# Acoustics_Board_Sheet_1.net
KiCad netlist of a schematic drawn in Altium Designer
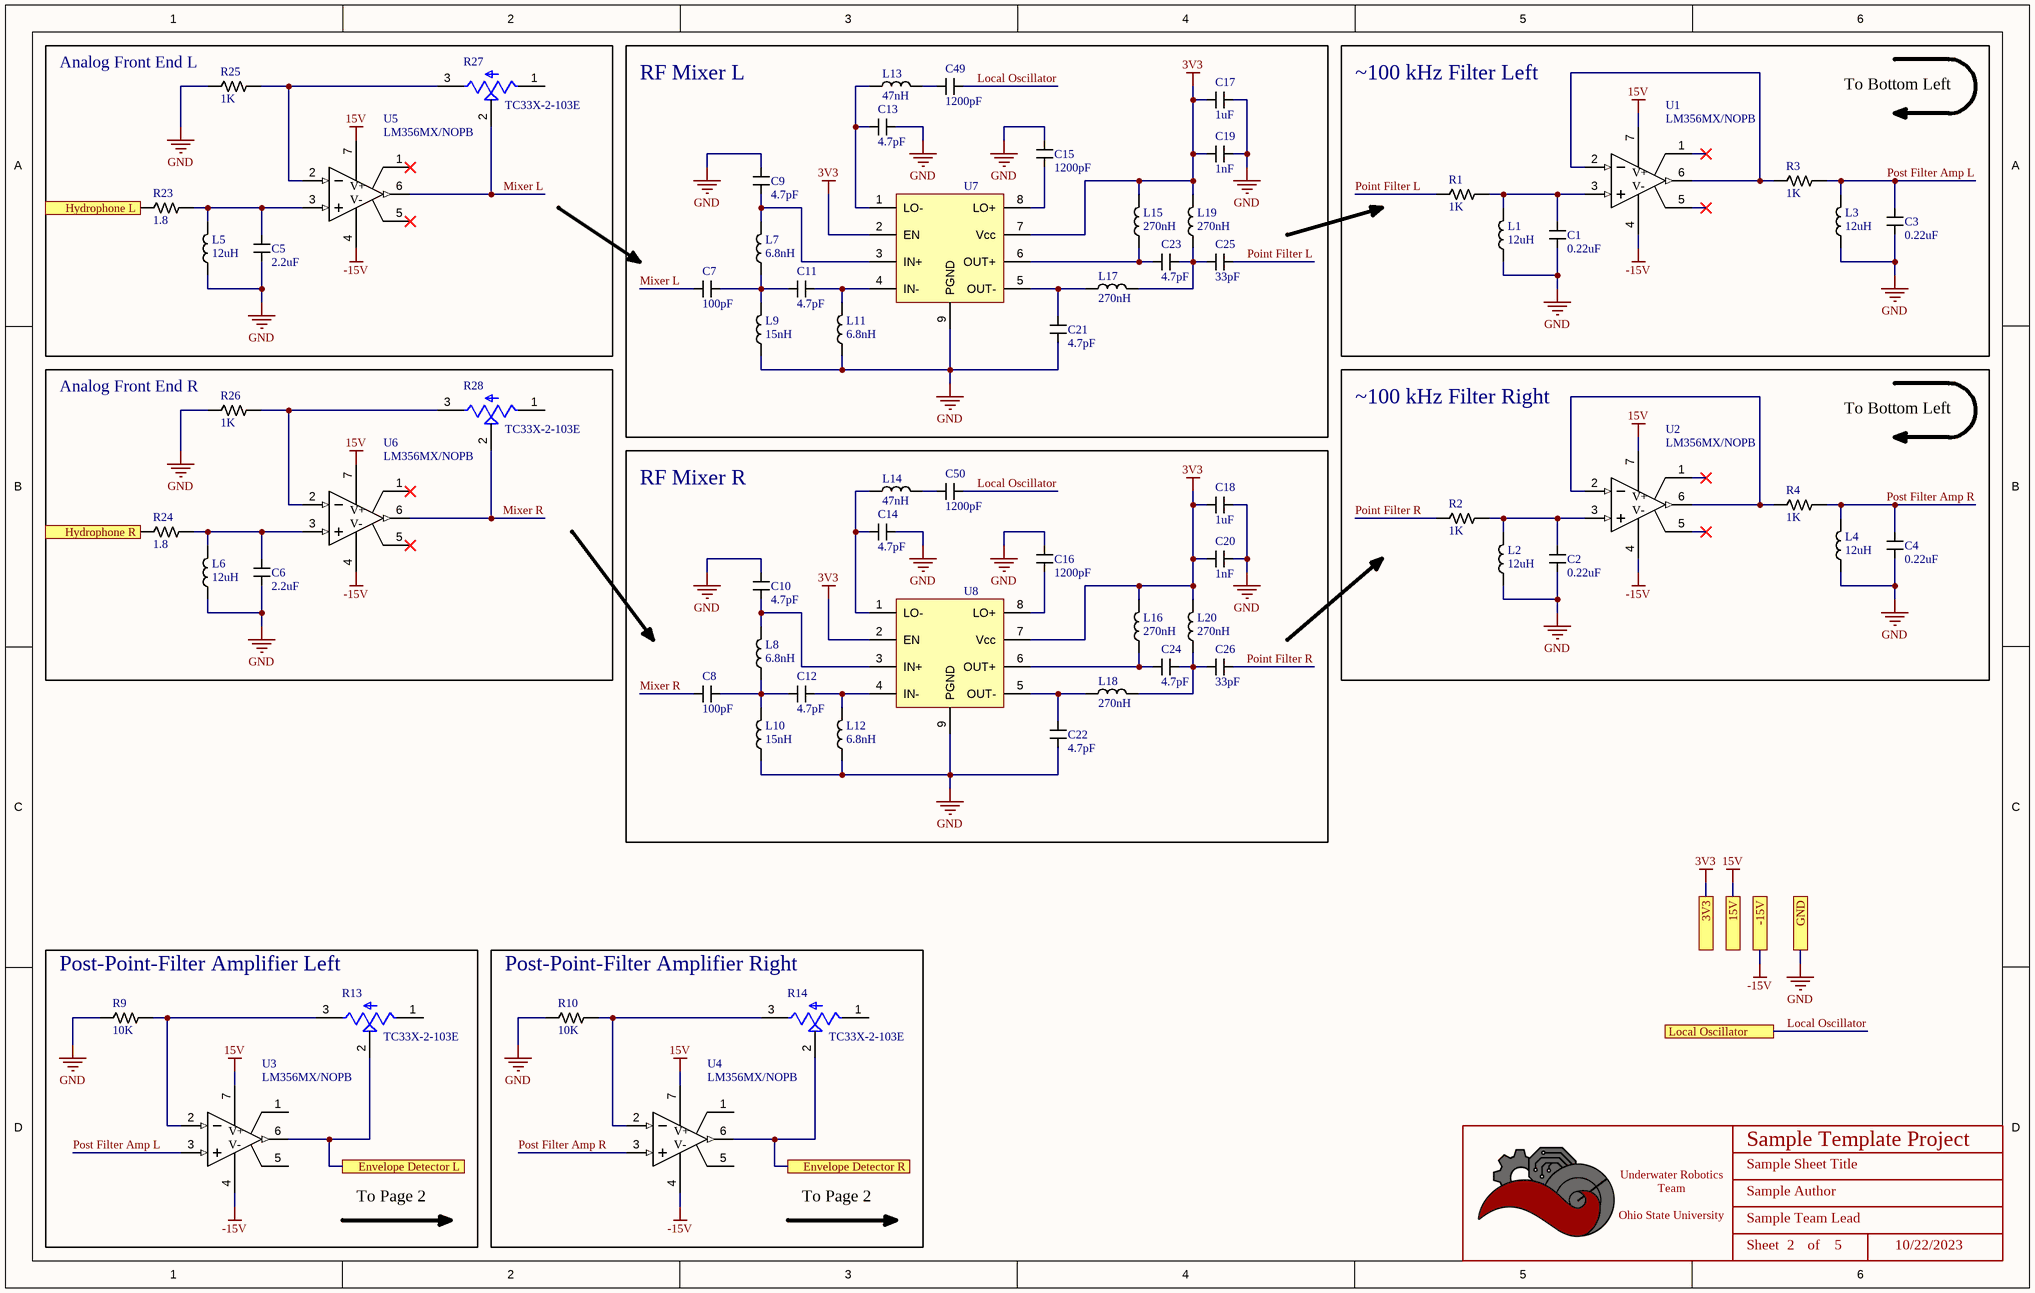
[diagram p0: Acoustics Board Sheet 1.SchDoc]

(export (version "E")
  (design (tool "Eeschema 10.0.6"))
  (components
    (comp (ref "C1")
      (value "0.22uF")
      (footprint "CAPACITOR_0603")
      (description "CAP CER 0.22uF 16V X7R 0603")
      (fields
        (field (name "TOLERANCE") "+/- 5%")
        (field (name "VOLTAGE") "16V")
        (field (name "MADE BY") "Nathan Ayer")
      )
      (libsource (lib "Capacitors") (part "CAPACITOR_0.000027uF_0603"))
    )
    (comp (ref "C2")
      (value "0.22uF")
      (footprint "CAPACITOR_0603")
      (description "CAP CER 0.22uF 16V X7R 0603")
      (fields
        (field (name "TOLERANCE") "+/- 5%")
        (field (name "VOLTAGE") "16V")
        (field (name "MADE BY") "Nathan Ayer")
      )
      (libsource (lib "Capacitors") (part "CAPACITOR_0.000027uF_0603"))
    )
    (comp (ref "C3")
      (value "0.22uF")
      (footprint "CAPACITOR_0603")
      (description "CAP CER 0.22uF 16V X7R 0603")
      (fields
        (field (name "TOLERANCE") "+/- 5%")
        (field (name "VOLTAGE") "16V")
        (field (name "MADE BY") "Nathan Ayer")
      )
      (libsource (lib "Capacitors") (part "CAPACITOR_0.000027uF_0603"))
    )
    (comp (ref "C4")
      (value "0.22uF")
      (footprint "CAPACITOR_0603")
      (description "CAP CER 0.22uF 16V X7R 0603")
      (fields
        (field (name "TOLERANCE") "+/- 5%")
        (field (name "VOLTAGE") "16V")
        (field (name "MADE BY") "Nathan Ayer")
      )
      (libsource (lib "Capacitors") (part "CAPACITOR_0.000027uF_0603"))
    )
    (comp (ref "C5")
      (value "2.2uF")
      (footprint "CAPACITOR_0603")
      (description "CAP CER 2.2PF 50V C0G/NP0 0603")
      (fields
        (field (name "TOLERANCE") "+/- 20%")
        (field (name "VOLTAGE") "6.3V")
        (field (name "MADE BY") "Flip B")
      )
      (libsource (lib "Capacitors") (part "CAPACITOR_22uF_0603"))
    )
    (comp (ref "C6")
      (value "2.2uF")
      (footprint "CAPACITOR_0603")
      (description "CAP CER 2.2PF 50V C0G/NP0 0603")
      (fields
        (field (name "TOLERANCE") "+/- 20%")
        (field (name "VOLTAGE") "6.3V")
        (field (name "MADE BY") "Flip B")
      )
      (libsource (lib "Capacitors") (part "CAPACITOR_22uF_0603"))
    )
    (comp (ref "C7")
      (value "100pF")
      (footprint "CAPACITOR_0402")
      (description "Cap 100pF 25V +/-10%\r\nCeramic 0402")
      (fields
        (field (name "TOLERANCE") "+/- 10%")
        (field (name "VOLTAGE") "25V")
        (field (name "MADE BY") "Robert Pafford")
      )
      (libsource (lib "Capacitors") (part "CAPACITOR_0.0001uF_0402"))
    )
    (comp (ref "C8")
      (value "100pF")
      (footprint "CAPACITOR_0402")
      (description "Cap 100pF 25V +/-10%\r\nCeramic 0402")
      (fields
        (field (name "TOLERANCE") "+/- 10%")
        (field (name "VOLTAGE") "25V")
        (field (name "MADE BY") "Robert Pafford")
      )
      (libsource (lib "Capacitors") (part "CAPACITOR_0.0001uF_0402"))
    )
    (comp (ref "C9")
      (value "4.7pF")
      (footprint "CAPACITOR_0402")
      (description "4.7 pF ±0.1pF 50V Ceramic Capacitor C0G, NP0 0402 (1005 Metric)")
      (fields (field (name "TOLERANCE") "+/- 0.1 pF") (field (name "VOLTAGE") "50V"))
      (libsource (lib "Capacitors") (part "CAPACITOR_0.000015uF_0402"))
    )
    (comp (ref "C10")
      (value "4.7pF")
      (footprint "CAPACITOR_0402")
      (description "4.7 pF ±0.1pF 50V Ceramic Capacitor C0G, NP0 0402 (1005 Metric)")
      (fields (field (name "TOLERANCE") "+/- 0.1 pF") (field (name "VOLTAGE") "50V"))
      (libsource (lib "Capacitors") (part "CAPACITOR_0.000015uF_0402"))
    )
    (comp (ref "C11")
      (value "4.7pF")
      (footprint "CAPACITOR_0402")
      (description "4.7 pF ±0.1pF 50V Ceramic Capacitor C0G, NP0 0402 (1005 Metric)")
      (fields (field (name "TOLERANCE") "+/- 0.1 pF") (field (name "VOLTAGE") "50V"))
      (libsource (lib "Capacitors") (part "CAPACITOR_0.000015uF_0402"))
    )
    (comp (ref "C12")
      (value "4.7pF")
      (footprint "CAPACITOR_0402")
      (description "4.7 pF ±0.1pF 50V Ceramic Capacitor C0G, NP0 0402 (1005 Metric)")
      (fields (field (name "TOLERANCE") "+/- 0.1 pF") (field (name "VOLTAGE") "50V"))
      (libsource (lib "Capacitors") (part "CAPACITOR_0.000015uF_0402"))
    )
    (comp (ref "C13")
      (value "4.7pF")
      (footprint "CAPACITOR_0402")
      (description "4.7 pF ±0.1pF 50V Ceramic Capacitor C0G, NP0 0402 (1005 Metric)")
      (fields (field (name "TOLERANCE") "+/- 0.1 pF") (field (name "VOLTAGE") "50V"))
      (libsource (lib "Capacitors") (part "CAPACITOR_0.000015uF_0402"))
    )
    (comp (ref "C14")
      (value "4.7pF")
      (footprint "CAPACITOR_0402")
      (description "4.7 pF ±0.1pF 50V Ceramic Capacitor C0G, NP0 0402 (1005 Metric)")
      (fields (field (name "TOLERANCE") "+/- 0.1 pF") (field (name "VOLTAGE") "50V"))
      (libsource (lib "Capacitors") (part "CAPACITOR_0.000015uF_0402"))
    )
    (comp (ref "C15")
      (value "1200pF")
      (footprint "CAPACITOR_0402")
      (description "CAP CER 1200PF 50V X7R 0402")
      (fields
        (field (name "TOLERANCE") "+/- 5%")
        (field (name "VOLTAGE") "50V")
        (field (name "MADE BY") "Robert Pafford")
      )
      (libsource (lib "Capacitors") (part "CAPACITOR_0.0012uF_0402"))
    )
    (comp (ref "C16")
      (value "1200pF")
      (footprint "CAPACITOR_0402")
      (description "CAP CER 1200PF 50V X7R 0402")
      (fields
        (field (name "TOLERANCE") "+/- 5%")
        (field (name "VOLTAGE") "50V")
        (field (name "MADE BY") "Robert Pafford")
      )
      (libsource (lib "Capacitors") (part "CAPACITOR_0.0012uF_0402"))
    )
    (comp (ref "C17")
      (value "1uF")
      (footprint "CAPACITOR_0603")
      (description "Cap 1uF 25V +/-10%\r\nCeramic 0603")
      (fields
        (field (name "TOLERANCE") "+/- 10%")
        (field (name "VOLTAGE") "16V")
        (field (name "MADE BY") "Flip B")
      )
      (libsource (lib "Capacitors") (part "CAPACITOR_1uF_0603_25V"))
    )
    (comp (ref "C18")
      (value "1uF")
      (footprint "CAPACITOR_0603")
      (description "Cap 1uF 25V +/-10%\r\nCeramic 0603")
      (fields
        (field (name "TOLERANCE") "+/- 10%")
        (field (name "VOLTAGE") "16V")
        (field (name "MADE BY") "Flip B")
      )
      (libsource (lib "Capacitors") (part "CAPACITOR_1uF_0603_25V"))
    )
    (comp (ref "C19")
      (value "1nF")
      (footprint "CAPACITOR_0603")
      (description "Cap 1000pF 50V +/-2%\r\nCeramic 0603")
      (fields
        (field (name "TOLERANCE") "+/- 2%")
        (field (name "VOLTAGE") "50")
        (field (name "MADE BY") "Flip B")
      )
      (libsource (lib "Capacitors") (part "CAPACITOR_0.001uF_0603"))
    )
    (comp (ref "C20")
      (value "1nF")
      (footprint "CAPACITOR_0603")
      (description "Cap 1000pF 50V +/-2%\r\nCeramic 0603")
      (fields
        (field (name "TOLERANCE") "+/- 2%")
        (field (name "VOLTAGE") "50")
        (field (name "MADE BY") "Flip B")
      )
      (libsource (lib "Capacitors") (part "CAPACITOR_0.001uF_0603"))
    )
    (comp (ref "C21")
      (value "4.7pF")
      (footprint "CAPACITOR_0402")
      (description "4.7 pF ±0.1pF 50V Ceramic Capacitor C0G, NP0 0402 (1005 Metric)")
      (fields (field (name "TOLERANCE") "+/- 0.1 pF") (field (name "VOLTAGE") "50V"))
      (libsource (lib "Capacitors") (part "CAPACITOR_0.000015uF_0402"))
    )
    (comp (ref "C22")
      (value "4.7pF")
      (footprint "CAPACITOR_0402")
      (description "4.7 pF ±0.1pF 50V Ceramic Capacitor C0G, NP0 0402 (1005 Metric)")
      (fields (field (name "TOLERANCE") "+/- 0.1 pF") (field (name "VOLTAGE") "50V"))
      (libsource (lib "Capacitors") (part "CAPACITOR_0.000015uF_0402"))
    )
    (comp (ref "C23")
      (value "4.7pF")
      (footprint "CAPACITOR_0402")
      (description "4.7 pF ±0.1pF 50V Ceramic Capacitor C0G, NP0 0402 (1005 Metric)")
      (fields (field (name "TOLERANCE") "+/- 0.1 pF") (field (name "VOLTAGE") "50V"))
      (libsource (lib "Capacitors") (part "CAPACITOR_0.000015uF_0402"))
    )
    (comp (ref "C24")
      (value "4.7pF")
      (footprint "CAPACITOR_0402")
      (description "4.7 pF ±0.1pF 50V Ceramic Capacitor C0G, NP0 0402 (1005 Metric)")
      (fields (field (name "TOLERANCE") "+/- 0.1 pF") (field (name "VOLTAGE") "50V"))
      (libsource (lib "Capacitors") (part "CAPACITOR_0.000015uF_0402"))
    )
    (comp (ref "C25")
      (value "33pF")
      (footprint "CAPACITOR_0603")
      (description "33 pF ±5% 250V Ceramic Capacitor C0G, NP0 0603 (1608 Metric)")
      (fields (field (name "TOLERANCE") "+/- 5%") (field (name "VOLTAGE") "250V"))
      (libsource (lib "Capacitors") (part "CAPACITOR_0.001uF_0603"))
    )
    (comp (ref "C26")
      (value "33pF")
      (footprint "CAPACITOR_0603")
      (description "33 pF ±5% 250V Ceramic Capacitor C0G, NP0 0603 (1608 Metric)")
      (fields (field (name "TOLERANCE") "+/- 5%") (field (name "VOLTAGE") "250V"))
      (libsource (lib "Capacitors") (part "CAPACITOR_0.001uF_0603"))
    )
    (comp (ref "C49")
      (value "1200pF")
      (footprint "CAPACITOR_0402")
      (description "CAP CER 1200PF 50V X7R 0402")
      (fields
        (field (name "TOLERANCE") "+/- 5%")
        (field (name "VOLTAGE") "50V")
        (field (name "MADE BY") "Robert Pafford")
      )
      (libsource (lib "Capacitors") (part "CAPACITOR_0.0012uF_0402"))
    )
    (comp (ref "C50")
      (value "1200pF")
      (footprint "CAPACITOR_0402")
      (description "CAP CER 1200PF 50V X7R 0402")
      (fields
        (field (name "TOLERANCE") "+/- 5%")
        (field (name "VOLTAGE") "50V")
        (field (name "MADE BY") "Robert Pafford")
      )
      (libsource (lib "Capacitors") (part "CAPACITOR_0.0012uF_0402"))
    )
    (comp (ref "L1")
      (value "12uH")
      (footprint "INDUCTOR_0603")
      (description "12 µH Shielded Multilayer Inductor 10 mA 1.8Ohm Max 0603 (1608 Metric)")
      (fields
        (field (name "TOLERANCE") "+/- 5%")
        (field (name "Comment") "FIXED IND 12UH 10MA 1.8 OHM SMD")
        (field (name "MADE BY") "Nathan Ayer")
      )
      (libsource (lib "Inductors") (part "INDUCTOR_12uH_0603"))
    )
    (comp (ref "L2")
      (value "12uH")
      (footprint "INDUCTOR_0603")
      (description "12 µH Shielded Multilayer Inductor 10 mA 1.8Ohm Max 0603 (1608 Metric)")
      (fields
        (field (name "TOLERANCE") "+/- 5%")
        (field (name "Comment") "FIXED IND 12UH 10MA 1.8 OHM SMD")
        (field (name "MADE BY") "Nathan Ayer")
      )
      (libsource (lib "Inductors") (part "INDUCTOR_12uH_0603"))
    )
    (comp (ref "L3")
      (value "12uH")
      (footprint "INDUCTOR_0603")
      (description "12 µH Shielded Multilayer Inductor 10 mA 1.8Ohm Max 0603 (1608 Metric)")
      (fields
        (field (name "TOLERANCE") "+/- 5%")
        (field (name "Comment") "FIXED IND 12UH 10MA 1.8 OHM SMD")
        (field (name "MADE BY") "Nathan Ayer")
      )
      (libsource (lib "Inductors") (part "INDUCTOR_12uH_0603"))
    )
    (comp (ref "L4")
      (value "12uH")
      (footprint "INDUCTOR_0603")
      (description "12 µH Shielded Multilayer Inductor 10 mA 1.8Ohm Max 0603 (1608 Metric)")
      (fields
        (field (name "TOLERANCE") "+/- 5%")
        (field (name "Comment") "FIXED IND 12UH 10MA 1.8 OHM SMD")
        (field (name "MADE BY") "Nathan Ayer")
      )
      (libsource (lib "Inductors") (part "INDUCTOR_12uH_0603"))
    )
    (comp (ref "L5")
      (value "12uH")
      (footprint "INDUCTOR_0603")
      (description "12 µH Shielded Multilayer Inductor 10 mA 1.8Ohm Max 0603 (1608 Metric)")
      (fields
        (field (name "TOLERANCE") "+/- 20%")
        (field (name "Comment") "FIXED IND 12UH 10MA 1.8 OHM SMD")
        (field (name "MADE BY") "Robert Pafford")
      )
      (libsource (lib "Inductors") (part "INDUCTOR_12uH_0603"))
    )
    (comp (ref "L6")
      (value "12uH")
      (footprint "INDUCTOR_0603")
      (description "12 µH Shielded Multilayer Inductor 10 mA 1.8Ohm Max 0603 (1608 Metric)")
      (fields
        (field (name "TOLERANCE") "+/- 20%")
        (field (name "Comment") "FIXED IND 12UH 10MA 1.8 OHM SMD")
        (field (name "MADE BY") "Robert Pafford")
      )
      (libsource (lib "Inductors") (part "INDUCTOR_12uH_0603"))
    )
    (comp (ref "L7")
      (value "6.8nH")
      (footprint "INDUCTOR_0402")
      (description "6.8 nH Unshielded Multilayer Inductor 250 mA 320mOhm Max 0402 (1005 Metric)")
      (fields (field (name "TOLERANCE") "+/- 5%") (field (name "Comment") "FIXED IND 6.8NH 250MA 320MOHM SM"))
      (libsource (lib "Inductors") (part "INDUCTOR_15nH_0402"))
    )
    (comp (ref "L8")
      (value "6.8nH")
      (footprint "INDUCTOR_0402")
      (description "6.8 nH Unshielded Multilayer Inductor 250 mA 320mOhm Max 0402 (1005 Metric)")
      (fields (field (name "TOLERANCE") "+/- 5%") (field (name "Comment") "FIXED IND 6.8NH 250MA 320MOHM SM"))
      (libsource (lib "Inductors") (part "INDUCTOR_15nH_0402"))
    )
    (comp (ref "L9")
      (value "15nH")
      (footprint "INDUCTOR_0402")
      (description "15 nH Unshielded Multilayer Inductor 250 mA 600mOhm Max 0402 (1005 Metric)")
      (fields (field (name "TOLERANCE") "+/- 5%") (field (name "Comment") "FIXED IND 15NH 250MA 600MOHM SMD"))
      (libsource (lib "Inductors") (part "INDUCTOR_15nH_0402"))
    )
    (comp (ref "L10")
      (value "15nH")
      (footprint "INDUCTOR_0402")
      (description "15 nH Unshielded Multilayer Inductor 250 mA 600mOhm Max 0402 (1005 Metric)")
      (fields (field (name "TOLERANCE") "+/- 5%") (field (name "Comment") "FIXED IND 15NH 250MA 600MOHM SMD"))
      (libsource (lib "Inductors") (part "INDUCTOR_15nH_0402"))
    )
    (comp (ref "L11")
      (value "6.8nH")
      (footprint "INDUCTOR_0402")
      (description "6.8 nH Unshielded Multilayer Inductor 250 mA 320mOhm Max 0402 (1005 Metric)")
      (fields (field (name "TOLERANCE") "+/- 5%") (field (name "Comment") "FIXED IND 6.8NH 250MA 320MOHM SM"))
      (libsource (lib "Inductors") (part "INDUCTOR_15nH_0402"))
    )
    (comp (ref "L12")
      (value "6.8nH")
      (footprint "INDUCTOR_0402")
      (description "6.8 nH Unshielded Multilayer Inductor 250 mA 320mOhm Max 0402 (1005 Metric)")
      (fields (field (name "TOLERANCE") "+/- 5%") (field (name "Comment") "FIXED IND 6.8NH 250MA 320MOHM SM"))
      (libsource (lib "Inductors") (part "INDUCTOR_15nH_0402"))
    )
    (comp (ref "L13")
      (value "47nH")
      (footprint "INDUCTOR_0402")
      (description "47 nH Unshielded Multilayer Inductor 200 mA 1.1Ohm Max 0402 (1005 Metric)")
      (fields (field (name "TOLERANCE") "+/- 5%") (field (name "Comment") "FIXED IND 47NH 200MA 1.1 OHM SMD"))
      (libsource (lib "Inductors") (part "INDUCTOR_15nH_0402"))
    )
    (comp (ref "L14")
      (value "47nH")
      (footprint "INDUCTOR_0402")
      (description "47 nH Unshielded Multilayer Inductor 200 mA 1.1Ohm Max 0402 (1005 Metric)")
      (fields (field (name "TOLERANCE") "+/- 5%") (field (name "Comment") "FIXED IND 47NH 200MA 1.1 OHM SMD"))
      (libsource (lib "Inductors") (part "INDUCTOR_15nH_0402"))
    )
    (comp (ref "L15")
      (value "270nH")
      (footprint "INDUCTOR_0402")
      (description "270 nH Unshielded Multilayer Inductor 110 mA 4.94Ohm Max 0402 (1005 Metric)")
      (fields
        (field (name "TOLERANCE") "+/- 10%")
        (field (name "Comment") "FIXED IND 270NH 110MA 4.94OHM SM")
      )
      (libsource (lib "Inductors") (part "INDUCTOR_15nH_0402"))
    )
    (comp (ref "L16")
      (value "270nH")
      (footprint "INDUCTOR_0402")
      (description "270 nH Unshielded Multilayer Inductor 110 mA 4.94Ohm Max 0402 (1005 Metric)")
      (fields
        (field (name "TOLERANCE") "+/- 10%")
        (field (name "Comment") "FIXED IND 270NH 110MA 4.94OHM SM")
      )
      (libsource (lib "Inductors") (part "INDUCTOR_15nH_0402"))
    )
    (comp (ref "L17")
      (value "270nH")
      (footprint "INDUCTOR_0402")
      (description "270 nH Unshielded Multilayer Inductor 110 mA 4.94Ohm Max 0402 (1005 Metric)")
      (fields
        (field (name "TOLERANCE") "+/- 10%")
        (field (name "Comment") "FIXED IND 270NH 110MA 4.94OHM SM")
      )
      (libsource (lib "Inductors") (part "INDUCTOR_15nH_0402"))
    )
    (comp (ref "L18")
      (value "270nH")
      (footprint "INDUCTOR_0402")
      (description "270 nH Unshielded Multilayer Inductor 110 mA 4.94Ohm Max 0402 (1005 Metric)")
      (fields
        (field (name "TOLERANCE") "+/- 10%")
        (field (name "Comment") "FIXED IND 270NH 110MA 4.94OHM SM")
      )
      (libsource (lib "Inductors") (part "INDUCTOR_15nH_0402"))
    )
    (comp (ref "L19")
      (value "270nH")
      (footprint "INDUCTOR_0402")
      (description "270 nH Unshielded Multilayer Inductor 110 mA 4.94Ohm Max 0402 (1005 Metric)")
      (fields
        (field (name "TOLERANCE") "+/- 10%")
        (field (name "Comment") "FIXED IND 270NH 110MA 4.94OHM SM")
      )
      (libsource (lib "Inductors") (part "INDUCTOR_15nH_0402"))
    )
    (comp (ref "L20")
      (value "270nH")
      (footprint "INDUCTOR_0402")
      (description "270 nH Unshielded Multilayer Inductor 110 mA 4.94Ohm Max 0402 (1005 Metric)")
      (fields
        (field (name "TOLERANCE") "+/- 10%")
        (field (name "Comment") "FIXED IND 270NH 110MA 4.94OHM SM")
      )
      (libsource (lib "Inductors") (part "INDUCTOR_15nH_0402"))
    )
    (comp (ref "R1")
      (value "1.45k Ohm 0.1% 1/10W")
      (footprint "RESISTOR_0603")
      (description "RES 1.45K OHM 0.1% 1/10W 0603")
      (fields
        (field (name "TOLERANCE") "+/- 0.1%")
        (field (name "VALUE  (OHMS)") "1K")
        (field (name "MADE BY") "Nathan Ayer")
      )
      (libsource (lib "Resistors") (part "RESISTOR_1K_0603"))
    )
    (comp (ref "R2")
      (value "1.45k Ohm 0.1% 1/10W")
      (footprint "RESISTOR_0603")
      (description "RES 1.45K OHM 0.1% 1/10W 0603")
      (fields
        (field (name "TOLERANCE") "+/- 0.1%")
        (field (name "VALUE  (OHMS)") "1K")
        (field (name "MADE BY") "Nathan Ayer")
      )
      (libsource (lib "Resistors") (part "RESISTOR_1K_0603"))
    )
    (comp (ref "R3")
      (value "1.45k Ohm 0.1% 1/10W")
      (footprint "RESISTOR_0603")
      (description "RES 1.45K OHM 0.1% 1/10W 0603")
      (fields
        (field (name "TOLERANCE") "+/- 0.1%")
        (field (name "VALUE  (OHMS)") "1K")
        (field (name "MADE BY") "Nathan Ayer")
      )
      (libsource (lib "Resistors") (part "RESISTOR_1K_0603"))
    )
    (comp (ref "R4")
      (value "1.45k Ohm 0.1% 1/10W")
      (footprint "RESISTOR_0603")
      (description "RES 1.45K OHM 0.1% 1/10W 0603")
      (fields
        (field (name "TOLERANCE") "+/- 0.1%")
        (field (name "VALUE  (OHMS)") "1K")
        (field (name "MADE BY") "Nathan Ayer")
      )
      (libsource (lib "Resistors") (part "RESISTOR_1K_0603"))
    )
    (comp (ref "R9")
      (value "10k Ohm 0.5% 1/10W")
      (footprint "RESISTOR_0603")
      (description "RES 10k OHM 0.5% 1/10W 0603")
      (fields
        (field (name "TOLERANCE") "+/- 0.5%")
        (field (name "VALUE  (OHMS)") "10K")
        (field (name "MADE BY") "Robert Pafford")
      )
      (libsource (lib "Resistors") (part "RESISTOR_10K_0.5%_0603"))
    )
    (comp (ref "R10")
      (value "10k Ohm 0.5% 1/10W")
      (footprint "RESISTOR_0603")
      (description "RES 10k OHM 0.5% 1/10W 0603")
      (fields
        (field (name "TOLERANCE") "+/- 0.5%")
        (field (name "VALUE  (OHMS)") "10K")
        (field (name "MADE BY") "Robert Pafford")
      )
      (libsource (lib "Resistors") (part "RESISTOR_10K_0.5%_0603"))
    )
    (comp (ref "R13")
      (value "TC33X-2-103E")
      (footprint "TRIM_TC33X-2-203E")
      (description "20 kOhms 0.1W, 1/10W J Lead Surface Mount Trimmer Potentiometer Cermet 1 Turn Top Adjustment")
      (fields (field (name "MF") "Bourns") (field (name "DIGI-KEY_PART_NUMBER") "TC33X-2-203ECT-ND"))
      (libsource (lib "Resistors") (part "TC33X-2-203E"))
    )
    (comp (ref "R14")
      (value "TC33X-2-103E")
      (footprint "TRIM_TC33X-2-203E")
      (description "20 kOhms 0.1W, 1/10W J Lead Surface Mount Trimmer Potentiometer Cermet 1 Turn Top Adjustment")
      (fields (field (name "MF") "Bourns") (field (name "DIGI-KEY_PART_NUMBER") "TC33X-2-203ECT-ND"))
      (libsource (lib "Resistors") (part "TC33X-2-203E"))
    )
    (comp (ref "R23")
      (value "2k Ohm 1% 1/16W")
      (footprint "RESISTOR_0402")
      (description "RES 2k OHM 1% 1/16W 0402")
      (fields
        (field (name "TOLERANCE") "+/- 1%")
        (field (name "VALUE  (OHMS)") "1.8")
        (field (name "MADE BY") "Flip B")
      )
      (libsource (lib "Resistors") (part "RESISTOR_2K_0402"))
    )
    (comp (ref "R24")
      (value "2k Ohm 1% 1/16W")
      (footprint "RESISTOR_0402")
      (description "RES 2k OHM 1% 1/16W 0402")
      (fields
        (field (name "TOLERANCE") "+/- 1%")
        (field (name "VALUE  (OHMS)") "1.8")
        (field (name "MADE BY") "Flip B")
      )
      (libsource (lib "Resistors") (part "RESISTOR_2K_0402"))
    )
    (comp (ref "R25")
      (value "1k Ohm 5% 1/8W")
      (footprint "RESISTOR_0603")
      (description "RES 1.8 OHM 5% 1/8W 0603")
      (fields
        (field (name "TOLERANCE") "+/- 5%")
        (field (name "VALUE  (OHMS)") "1K")
        (field (name "MADE BY") "Robert Pafford")
      )
      (libsource (lib "Resistors") (part "RESISTOR_1K_0603"))
    )
    (comp (ref "R26")
      (value "1k Ohm 5% 1/8W")
      (footprint "RESISTOR_0603")
      (description "RES 1k OHM 5% 1/8W 0603")
      (fields
        (field (name "TOLERANCE") "+/- 5%")
        (field (name "VALUE  (OHMS)") "1K")
        (field (name "MADE BY") "Robert Pafford")
      )
      (libsource (lib "Resistors") (part "RESISTOR_1K_0603"))
    )
    (comp (ref "R27")
      (value "TC33X-2-103E")
      (footprint "TRIM_TC33X-2-203E")
      (description "20 kOhms 0.1W, 1/10W J Lead Surface Mount Trimmer Potentiometer Cermet 1 Turn Top Adjustment")
      (fields (field (name "MF") "Bourns") (field (name "DIGI-KEY_PART_NUMBER") "TC33X-2-203ECT-ND"))
      (libsource (lib "Resistors") (part "TC33X-2-203E"))
    )
    (comp (ref "R28")
      (value "TC33X-2-103E")
      (footprint "TRIM_TC33X-2-203E")
      (description "20 kOhms 0.1W, 1/10W J Lead Surface Mount Trimmer Potentiometer Cermet 1 Turn Top Adjustment")
      (fields (field (name "MF") "Bourns") (field (name "DIGI-KEY_PART_NUMBER") "TC33X-2-203ECT-ND"))
      (libsource (lib "Resistors") (part "TC33X-2-203E"))
    )
    (comp (ref "U1")
      (value "LM356MX/NOPB")
      (footprint "SOIC-8")
      (description "IC OPAMP JFET 1 CIRCUIT 8SOIC")
      (fields
        (field (name "PARTNUMBER") "LM8261M5X/NOPB")
        (field (name "MANUFACTURER") "Texas Instruments")
        (field (name "CREATED BY") "Dylan T")
      )
      (libsource (lib "Integrated Circuits") (part "LM356MX/NOPB"))
    )
    (comp (ref "U2")
      (value "LM356MX/NOPB")
      (footprint "SOIC-8")
      (description "IC OPAMP JFET 1 CIRCUIT 8SOIC")
      (fields
        (field (name "PARTNUMBER") "LM8261M5X/NOPB")
        (field (name "MANUFACTURER") "Texas Instruments")
        (field (name "CREATED BY") "Dylan T")
      )
      (libsource (lib "Integrated Circuits") (part "LM356MX/NOPB"))
    )
    (comp (ref "U3")
      (value "LM356MX/NOPB")
      (footprint "SOIC-8")
      (description "IC OPAMP JFET 1 CIRCUIT 8SOIC")
      (fields
        (field (name "PARTNUMBER") "LM8261M5X/NOPB")
        (field (name "MANUFACTURER") "Texas Instruments")
        (field (name "CREATED BY") "Dylan T")
      )
      (libsource (lib "Integrated Circuits") (part "LM356MX/NOPB"))
    )
    (comp (ref "U4")
      (value "LM356MX/NOPB")
      (footprint "SOIC-8")
      (description "IC OPAMP JFET 1 CIRCUIT 8SOIC")
      (fields
        (field (name "PARTNUMBER") "LM8261M5X/NOPB")
        (field (name "MANUFACTURER") "Texas Instruments")
        (field (name "CREATED BY") "Dylan T")
      )
      (libsource (lib "Integrated Circuits") (part "LM356MX/NOPB"))
    )
    (comp (ref "U5")
      (value "LM356MX/NOPB")
      (footprint "SOIC-8")
      (description "IC OPAMP JFET 1 CIRCUIT 8SOIC")
      (fields
        (field (name "PARTNUMBER") "LM8261M5X/NOPB")
        (field (name "MANUFACTURER") "Texas Instruments")
        (field (name "CREATED BY") "Dylan T")
      )
      (libsource (lib "Integrated Circuits") (part "LM356MX/NOPB"))
    )
    (comp (ref "U6")
      (value "LM356MX/NOPB")
      (footprint "SOIC-8")
      (description "IC OPAMP JFET 1 CIRCUIT 8SOIC")
      (fields
        (field (name "PARTNUMBER") "LM8261M5X/NOPB")
        (field (name "MANUFACTURER") "Texas Instruments")
        (field (name "CREATED BY") "Dylan T")
      )
      (libsource (lib "Integrated Circuits") (part "LM356MX/NOPB"))
    )
    (comp (ref "U7")
      (value "LT5560EDD")
      (footprint "LT5560EDD")
      (description "RF Mixer IC CATV, DBS, PHS, UHF, VHF Up/Down Converter 10kHz ~ 4GHz 8-DFN (3x3)")
      (libsource (lib "Integrated Circuits") (part "LT5560EDD"))
    )
    (comp (ref "U8")
      (value "LT5560EDD")
      (footprint "LT5560EDD")
      (description "RF Mixer IC CATV, DBS, PHS, UHF, VHF Up/Down Converter 10kHz ~ 4GHz 8-DFN (3x3)")
      (libsource (lib "Integrated Circuits") (part "LT5560EDD"))
    )
  )
  (nets
    (net (code "1") (name "-15V") (class "Default")
      (node (ref "U1") (pin "4") (pinfunction "V-_4") (pintype "power_in"))
      (node (ref "U2") (pin "4") (pinfunction "V-_4") (pintype "power_in"))
      (node (ref "U3") (pin "4") (pinfunction "V-_4") (pintype "power_in"))
      (node (ref "U4") (pin "4") (pinfunction "V-_4") (pintype "power_in"))
      (node (ref "U5") (pin "4") (pinfunction "V-_4") (pintype "power_in"))
      (node (ref "U6") (pin "4") (pinfunction "V-_4") (pintype "power_in"))
    )
    (net (code "3") (name "/Envelope Detector L") (class "Default")
      (node (ref "R13") (pin "2") (pinfunction "W_2") (pintype "passive"))
      (node (ref "U3") (pin "6") (pinfunction "OUT_6") (pintype "output"))
    )
    (net (code "4") (name "/Envelope Detector R") (class "Default")
      (node (ref "R14") (pin "2") (pinfunction "W_2") (pintype "passive"))
      (node (ref "U4") (pin "6") (pinfunction "OUT_6") (pintype "output"))
    )
    (net (code "5") (name "/Hydrophone L") (class "Default")
      (node (ref "R23") (pin "2") (pinfunction "2_2") (pintype "passive"))
    )
    (net (code "6") (name "/Hydrophone R") (class "Default")
      (node (ref "R24") (pin "2") (pinfunction "2_2") (pintype "passive"))
    )
    (net (code "7") (name "/Local Oscillator") (class "Default")
      (node (ref "C49") (pin "1") (pinfunction "1_1") (pintype "passive"))
      (node (ref "C50") (pin "1") (pinfunction "1_1") (pintype "passive"))
    )
    (net (code "8") (name "/Mixer L") (class "Default")
      (node (ref "C7") (pin "1") (pinfunction "1_1") (pintype "passive"))
      (node (ref "R27") (pin "2") (pinfunction "W_2") (pintype "passive"))
      (node (ref "U5") (pin "6") (pinfunction "OUT_6") (pintype "output"))
    )
    (net (code "9") (name "/Mixer R") (class "Default")
      (node (ref "C8") (pin "1") (pinfunction "1_1") (pintype "passive"))
      (node (ref "R28") (pin "2") (pinfunction "W_2") (pintype "passive"))
      (node (ref "U6") (pin "6") (pinfunction "OUT_6") (pintype "output"))
    )
    (net (code "10") (name "/Point Filter L") (class "Default")
      (node (ref "C25") (pin "1") (pinfunction "1_1") (pintype "passive"))
      (node (ref "R1") (pin "2") (pinfunction "2_2") (pintype "passive"))
    )
    (net (code "11") (name "/Point Filter R") (class "Default")
      (node (ref "C26") (pin "1") (pinfunction "1_1") (pintype "passive"))
      (node (ref "R2") (pin "2") (pinfunction "2_2") (pintype "passive"))
    )
    (net (code "12") (name "/Post Filter Amp L") (class "Default")
      (node (ref "C3") (pin "1") (pinfunction "1_1") (pintype "passive"))
      (node (ref "L3") (pin "1") (pinfunction "1_1") (pintype "passive"))
      (node (ref "R3") (pin "1") (pinfunction "1_1") (pintype "passive"))
      (node (ref "U3") (pin "3") (pinfunction "IN+_3") (pintype "input"))
    )
    (net (code "13") (name "/Post Filter Amp R") (class "Default")
      (node (ref "C4") (pin "1") (pinfunction "1_1") (pintype "passive"))
      (node (ref "L4") (pin "1") (pinfunction "1_1") (pintype "passive"))
      (node (ref "R4") (pin "1") (pinfunction "1_1") (pintype "passive"))
      (node (ref "U4") (pin "3") (pinfunction "IN+_3") (pintype "input"))
    )
    (net (code "14") (name "3V3") (class "Default")
      (node (ref "C17") (pin "2") (pinfunction "2_2") (pintype "passive"))
      (node (ref "C18") (pin "2") (pinfunction "2_2") (pintype "passive"))
      (node (ref "C19") (pin "2") (pinfunction "2_2") (pintype "passive"))
      (node (ref "C20") (pin "2") (pinfunction "2_2") (pintype "passive"))
      (node (ref "L15") (pin "1") (pinfunction "1_1") (pintype "passive"))
      (node (ref "L16") (pin "1") (pinfunction "1_1") (pintype "passive"))
      (node (ref "L19") (pin "1") (pinfunction "1_1") (pintype "passive"))
      (node (ref "L20") (pin "1") (pinfunction "1_1") (pintype "passive"))
      (node (ref "U7") (pin "2") (pinfunction "EN_2") (pintype "passive"))
      (node (ref "U7") (pin "7") (pinfunction "Vcc_7") (pintype "passive"))
      (node (ref "U8") (pin "2") (pinfunction "EN_2") (pintype "passive"))
      (node (ref "U8") (pin "7") (pinfunction "Vcc_7") (pintype "passive"))
    )
    (net (code "15") (name "15V") (class "Default")
      (node (ref "U1") (pin "7") (pinfunction "V+_7") (pintype "power_in"))
      (node (ref "U2") (pin "7") (pinfunction "V+_7") (pintype "power_in"))
      (node (ref "U3") (pin "7") (pinfunction "V+_7") (pintype "power_in"))
      (node (ref "U4") (pin "7") (pinfunction "V+_7") (pintype "power_in"))
      (node (ref "U5") (pin "7") (pinfunction "V+_7") (pintype "power_in"))
      (node (ref "U6") (pin "7") (pinfunction "V+_7") (pintype "power_in"))
    )
    (net (code "16") (name "GND") (class "Default")
      (node (ref "C1") (pin "2") (pinfunction "2_2") (pintype "passive"))
      (node (ref "C10") (pin "1") (pinfunction "1_1") (pintype "passive"))
      (node (ref "C13") (pin "1") (pinfunction "1_1") (pintype "passive"))
      (node (ref "C14") (pin "1") (pinfunction "1_1") (pintype "passive"))
      (node (ref "C15") (pin "1") (pinfunction "1_1") (pintype "passive"))
      (node (ref "C16") (pin "1") (pinfunction "1_1") (pintype "passive"))
      (node (ref "C17") (pin "1") (pinfunction "1_1") (pintype "passive"))
      (node (ref "C18") (pin "1") (pinfunction "1_1") (pintype "passive"))
      (node (ref "C19") (pin "1") (pinfunction "1_1") (pintype "passive"))
      (node (ref "C2") (pin "2") (pinfunction "2_2") (pintype "passive"))
      (node (ref "C20") (pin "1") (pinfunction "1_1") (pintype "passive"))
      (node (ref "C21") (pin "2") (pinfunction "2_2") (pintype "passive"))
      (node (ref "C22") (pin "2") (pinfunction "2_2") (pintype "passive"))
      (node (ref "C3") (pin "2") (pinfunction "2_2") (pintype "passive"))
      (node (ref "C4") (pin "2") (pinfunction "2_2") (pintype "passive"))
      (node (ref "C5") (pin "2") (pinfunction "2_2") (pintype "passive"))
      (node (ref "C6") (pin "2") (pinfunction "2_2") (pintype "passive"))
      (node (ref "C9") (pin "1") (pinfunction "1_1") (pintype "passive"))
      (node (ref "L1") (pin "2") (pinfunction "2_2") (pintype "passive"))
      (node (ref "L10") (pin "2") (pinfunction "2_2") (pintype "passive"))
      (node (ref "L11") (pin "2") (pinfunction "2_2") (pintype "passive"))
      (node (ref "L12") (pin "2") (pinfunction "2_2") (pintype "passive"))
      (node (ref "L2") (pin "2") (pinfunction "2_2") (pintype "passive"))
      (node (ref "L3") (pin "2") (pinfunction "2_2") (pintype "passive"))
      (node (ref "L4") (pin "2") (pinfunction "2_2") (pintype "passive"))
      (node (ref "L5") (pin "2") (pinfunction "2_2") (pintype "passive"))
      (node (ref "L6") (pin "2") (pinfunction "2_2") (pintype "passive"))
      (node (ref "L9") (pin "2") (pinfunction "2_2") (pintype "passive"))
      (node (ref "R10") (pin "2") (pinfunction "2_2") (pintype "passive"))
      (node (ref "R25") (pin "2") (pinfunction "2_2") (pintype "passive"))
      (node (ref "R26") (pin "2") (pinfunction "2_2") (pintype "passive"))
      (node (ref "R9") (pin "2") (pinfunction "2_2") (pintype "passive"))
      (node (ref "U7") (pin "9") (pinfunction "PGND_9") (pintype "passive"))
      (node (ref "U8") (pin "9") (pinfunction "PGND_9") (pintype "passive"))
    )
    (net (code "17") (name "Net-(C11-Pad2)") (class "Default")
      (node (ref "C11") (pin "2") (pinfunction "2_2") (pintype "passive"))
      (node (ref "C7") (pin "2") (pinfunction "2_2") (pintype "passive"))
      (node (ref "L7") (pin "2") (pinfunction "2_2") (pintype "passive"))
      (node (ref "L9") (pin "1") (pinfunction "1_1") (pintype "passive"))
    )
    (net (code "18") (name "Net-(C12-Pad2)") (class "Default")
      (node (ref "C12") (pin "2") (pinfunction "2_2") (pintype "passive"))
      (node (ref "C8") (pin "2") (pinfunction "2_2") (pintype "passive"))
      (node (ref "L10") (pin "1") (pinfunction "1_1") (pintype "passive"))
      (node (ref "L8") (pin "2") (pinfunction "2_2") (pintype "passive"))
    )
    (net (code "19") (name "Net-(C23-Pad1)") (class "Default")
      (node (ref "C23") (pin "1") (pinfunction "1_1") (pintype "passive"))
      (node (ref "C25") (pin "2") (pinfunction "2_2") (pintype "passive"))
      (node (ref "L17") (pin "1") (pinfunction "1_1") (pintype "passive"))
      (node (ref "L19") (pin "2") (pinfunction "2_2") (pintype "passive"))
    )
    (net (code "20") (name "Net-(C24-Pad1)") (class "Default")
      (node (ref "C24") (pin "1") (pinfunction "1_1") (pintype "passive"))
      (node (ref "C26") (pin "2") (pinfunction "2_2") (pintype "passive"))
      (node (ref "L18") (pin "1") (pinfunction "1_1") (pintype "passive"))
      (node (ref "L20") (pin "2") (pinfunction "2_2") (pintype "passive"))
    )
    (net (code "21") (name "Net-(C49-Pad2)") (class "Default")
      (node (ref "C49") (pin "2") (pinfunction "2_2") (pintype "passive"))
      (node (ref "L13") (pin "1") (pinfunction "1_1") (pintype "passive"))
    )
    (net (code "22") (name "Net-(C50-Pad2)") (class "Default")
      (node (ref "C50") (pin "2") (pinfunction "2_2") (pintype "passive"))
      (node (ref "L14") (pin "1") (pinfunction "1_1") (pintype "passive"))
    )
    (net (code "23") (name "Net-(R13-CW)") (class "Default")
      (node (ref "R13") (pin "3") (pinfunction "CW_3") (pintype "passive"))
      (node (ref "R9") (pin "1") (pinfunction "1_1") (pintype "passive"))
      (node (ref "U3") (pin "2") (pinfunction "IN-_2") (pintype "input"))
    )
    (net (code "24") (name "Net-(R14-CW)") (class "Default")
      (node (ref "R10") (pin "1") (pinfunction "1_1") (pintype "passive"))
      (node (ref "R14") (pin "3") (pinfunction "CW_3") (pintype "passive"))
      (node (ref "U4") (pin "2") (pinfunction "IN-_2") (pintype "input"))
    )
    (net (code "25") (name "Net-(R27-CW)") (class "Default")
      (node (ref "R25") (pin "1") (pinfunction "1_1") (pintype "passive"))
      (node (ref "R27") (pin "3") (pinfunction "CW_3") (pintype "passive"))
      (node (ref "U5") (pin "2") (pinfunction "IN-_2") (pintype "input"))
    )
    (net (code "26") (name "Net-(R28-CW)") (class "Default")
      (node (ref "R26") (pin "1") (pinfunction "1_1") (pintype "passive"))
      (node (ref "R28") (pin "3") (pinfunction "CW_3") (pintype "passive"))
      (node (ref "U6") (pin "2") (pinfunction "IN-_2") (pintype "input"))
    )
    (net (code "27") (name "Net-(U1-IN+)") (class "Default")
      (node (ref "C1") (pin "1") (pinfunction "1_1") (pintype "passive"))
      (node (ref "L1") (pin "1") (pinfunction "1_1") (pintype "passive"))
      (node (ref "R1") (pin "1") (pinfunction "1_1") (pintype "passive"))
      (node (ref "U1") (pin "3") (pinfunction "IN+_3") (pintype "input"))
    )
    (net (code "28") (name "Net-(U1-IN-)") (class "Default")
      (node (ref "R3") (pin "2") (pinfunction "2_2") (pintype "passive"))
      (node (ref "U1") (pin "2") (pinfunction "IN-_2") (pintype "input"))
      (node (ref "U1") (pin "6") (pinfunction "OUT_6") (pintype "output"))
    )
    (net (code "29") (name "Net-(U2-IN+)") (class "Default")
      (node (ref "C2") (pin "1") (pinfunction "1_1") (pintype "passive"))
      (node (ref "L2") (pin "1") (pinfunction "1_1") (pintype "passive"))
      (node (ref "R2") (pin "1") (pinfunction "1_1") (pintype "passive"))
      (node (ref "U2") (pin "3") (pinfunction "IN+_3") (pintype "input"))
    )
    (net (code "30") (name "Net-(U2-IN-)") (class "Default")
      (node (ref "R4") (pin "2") (pinfunction "2_2") (pintype "passive"))
      (node (ref "U2") (pin "2") (pinfunction "IN-_2") (pintype "input"))
      (node (ref "U2") (pin "6") (pinfunction "OUT_6") (pintype "output"))
    )
    (net (code "31") (name "Net-(U5-IN+)") (class "Default")
      (node (ref "C5") (pin "1") (pinfunction "1_1") (pintype "passive"))
      (node (ref "L5") (pin "1") (pinfunction "1_1") (pintype "passive"))
      (node (ref "R23") (pin "1") (pinfunction "1_1") (pintype "passive"))
      (node (ref "U5") (pin "3") (pinfunction "IN+_3") (pintype "input"))
    )
    (net (code "32") (name "Net-(U6-IN+)") (class "Default")
      (node (ref "C6") (pin "1") (pinfunction "1_1") (pintype "passive"))
      (node (ref "L6") (pin "1") (pinfunction "1_1") (pintype "passive"))
      (node (ref "R24") (pin "1") (pinfunction "1_1") (pintype "passive"))
      (node (ref "U6") (pin "3") (pinfunction "IN+_3") (pintype "input"))
    )
    (net (code "33") (name "Net-(U7-IN+)") (class "Default")
      (node (ref "C9") (pin "2") (pinfunction "2_2") (pintype "passive"))
      (node (ref "L7") (pin "1") (pinfunction "1_1") (pintype "passive"))
      (node (ref "U7") (pin "3") (pinfunction "IN+_3") (pintype "passive"))
    )
    (net (code "34") (name "Net-(U7-IN-)") (class "Default")
      (node (ref "C11") (pin "1") (pinfunction "1_1") (pintype "passive"))
      (node (ref "L11") (pin "1") (pinfunction "1_1") (pintype "passive"))
      (node (ref "U7") (pin "4") (pinfunction "IN-_4") (pintype "passive"))
    )
    (net (code "35") (name "Net-(U7-LO+)") (class "Default")
      (node (ref "C15") (pin "2") (pinfunction "2_2") (pintype "passive"))
      (node (ref "U7") (pin "8") (pinfunction "LO+_8") (pintype "passive"))
    )
    (net (code "36") (name "Net-(U7-LO-)") (class "Default")
      (node (ref "C13") (pin "2") (pinfunction "2_2") (pintype "passive"))
      (node (ref "L13") (pin "2") (pinfunction "2_2") (pintype "passive"))
      (node (ref "U7") (pin "1") (pinfunction "LO-_1") (pintype "passive"))
    )
    (net (code "37") (name "Net-(U7-OUT+)") (class "Default")
      (node (ref "C23") (pin "2") (pinfunction "2_2") (pintype "passive"))
      (node (ref "L15") (pin "2") (pinfunction "2_2") (pintype "passive"))
      (node (ref "U7") (pin "6") (pinfunction "OUT+_6") (pintype "passive"))
    )
    (net (code "38") (name "Net-(U7-OUT-)") (class "Default")
      (node (ref "C21") (pin "1") (pinfunction "1_1") (pintype "passive"))
      (node (ref "L17") (pin "2") (pinfunction "2_2") (pintype "passive"))
      (node (ref "U7") (pin "5") (pinfunction "OUT-_5") (pintype "passive"))
    )
    (net (code "39") (name "Net-(U8-IN+)") (class "Default")
      (node (ref "C10") (pin "2") (pinfunction "2_2") (pintype "passive"))
      (node (ref "L8") (pin "1") (pinfunction "1_1") (pintype "passive"))
      (node (ref "U8") (pin "3") (pinfunction "IN+_3") (pintype "passive"))
    )
    (net (code "40") (name "Net-(U8-IN-)") (class "Default")
      (node (ref "C12") (pin "1") (pinfunction "1_1") (pintype "passive"))
      (node (ref "L12") (pin "1") (pinfunction "1_1") (pintype "passive"))
      (node (ref "U8") (pin "4") (pinfunction "IN-_4") (pintype "passive"))
    )
    (net (code "41") (name "Net-(U8-LO+)") (class "Default")
      (node (ref "C16") (pin "2") (pinfunction "2_2") (pintype "passive"))
      (node (ref "U8") (pin "8") (pinfunction "LO+_8") (pintype "passive"))
    )
    (net (code "42") (name "Net-(U8-LO-)") (class "Default")
      (node (ref "C14") (pin "2") (pinfunction "2_2") (pintype "passive"))
      (node (ref "L14") (pin "2") (pinfunction "2_2") (pintype "passive"))
      (node (ref "U8") (pin "1") (pinfunction "LO-_1") (pintype "passive"))
    )
    (net (code "43") (name "Net-(U8-OUT+)") (class "Default")
      (node (ref "C24") (pin "2") (pinfunction "2_2") (pintype "passive"))
      (node (ref "L16") (pin "2") (pinfunction "2_2") (pintype "passive"))
      (node (ref "U8") (pin "6") (pinfunction "OUT+_6") (pintype "passive"))
    )
    (net (code "44") (name "Net-(U8-OUT-)") (class "Default")
      (node (ref "C22") (pin "1") (pinfunction "1_1") (pintype "passive"))
      (node (ref "L18") (pin "2") (pinfunction "2_2") (pintype "passive"))
      (node (ref "U8") (pin "5") (pinfunction "OUT-_5") (pintype "passive"))
    )
    (net (code "45") (name "unconnected-(R13-CCW-Pad1)") (class "Default")
      (node (ref "R13") (pin "1") (pinfunction "CCW_1") (pintype "passive"))
    )
    (net (code "46") (name "unconnected-(R14-CCW-Pad1)") (class "Default")
      (node (ref "R14") (pin "1") (pinfunction "CCW_1") (pintype "passive"))
    )
    (net (code "47") (name "unconnected-(R27-CCW-Pad1)") (class "Default")
      (node (ref "R27") (pin "1") (pinfunction "CCW_1") (pintype "passive"))
    )
    (net (code "48") (name "unconnected-(R28-CCW-Pad1)") (class "Default")
      (node (ref "R28") (pin "1") (pinfunction "CCW_1") (pintype "passive"))
    )
    (net (code "49") (name "unconnected-(U1-Balance-Pad1)") (class "Default")
      (node (ref "U1") (pin "1") (pinfunction "Balance_1") (pintype "passive+no_connect"))
    )
    (net (code "50") (name "unconnected-(U1-Balance-Pad5)") (class "Default")
      (node (ref "U1") (pin "5") (pinfunction "Balance_5") (pintype "passive+no_connect"))
    )
    (net (code "51") (name "unconnected-(U2-Balance-Pad1)") (class "Default")
      (node (ref "U2") (pin "1") (pinfunction "Balance_1") (pintype "passive+no_connect"))
    )
    (net (code "52") (name "unconnected-(U2-Balance-Pad5)") (class "Default")
      (node (ref "U2") (pin "5") (pinfunction "Balance_5") (pintype "passive+no_connect"))
    )
    (net (code "53") (name "unconnected-(U3-Balance-Pad1)") (class "Default")
      (node (ref "U3") (pin "1") (pinfunction "Balance_1") (pintype "passive"))
    )
    (net (code "54") (name "unconnected-(U3-Balance-Pad5)") (class "Default")
      (node (ref "U3") (pin "5") (pinfunction "Balance_5") (pintype "passive"))
    )
    (net (code "55") (name "unconnected-(U4-Balance-Pad1)") (class "Default")
      (node (ref "U4") (pin "1") (pinfunction "Balance_1") (pintype "passive"))
    )
    (net (code "56") (name "unconnected-(U4-Balance-Pad5)") (class "Default")
      (node (ref "U4") (pin "5") (pinfunction "Balance_5") (pintype "passive"))
    )
    (net (code "57") (name "unconnected-(U5-Balance-Pad1)") (class "Default")
      (node (ref "U5") (pin "1") (pinfunction "Balance_1") (pintype "passive+no_connect"))
    )
    (net (code "58") (name "unconnected-(U5-Balance-Pad5)") (class "Default")
      (node (ref "U5") (pin "5") (pinfunction "Balance_5") (pintype "passive+no_connect"))
    )
    (net (code "59") (name "unconnected-(U6-Balance-Pad1)") (class "Default")
      (node (ref "U6") (pin "1") (pinfunction "Balance_1") (pintype "passive+no_connect"))
    )
    (net (code "60") (name "unconnected-(U6-Balance-Pad5)") (class "Default")
      (node (ref "U6") (pin "5") (pinfunction "Balance_5") (pintype "passive+no_connect"))
    )
  )
)
